# Athena-r0p1.net
KiCad netlist of a schematic drawn in EAGLE
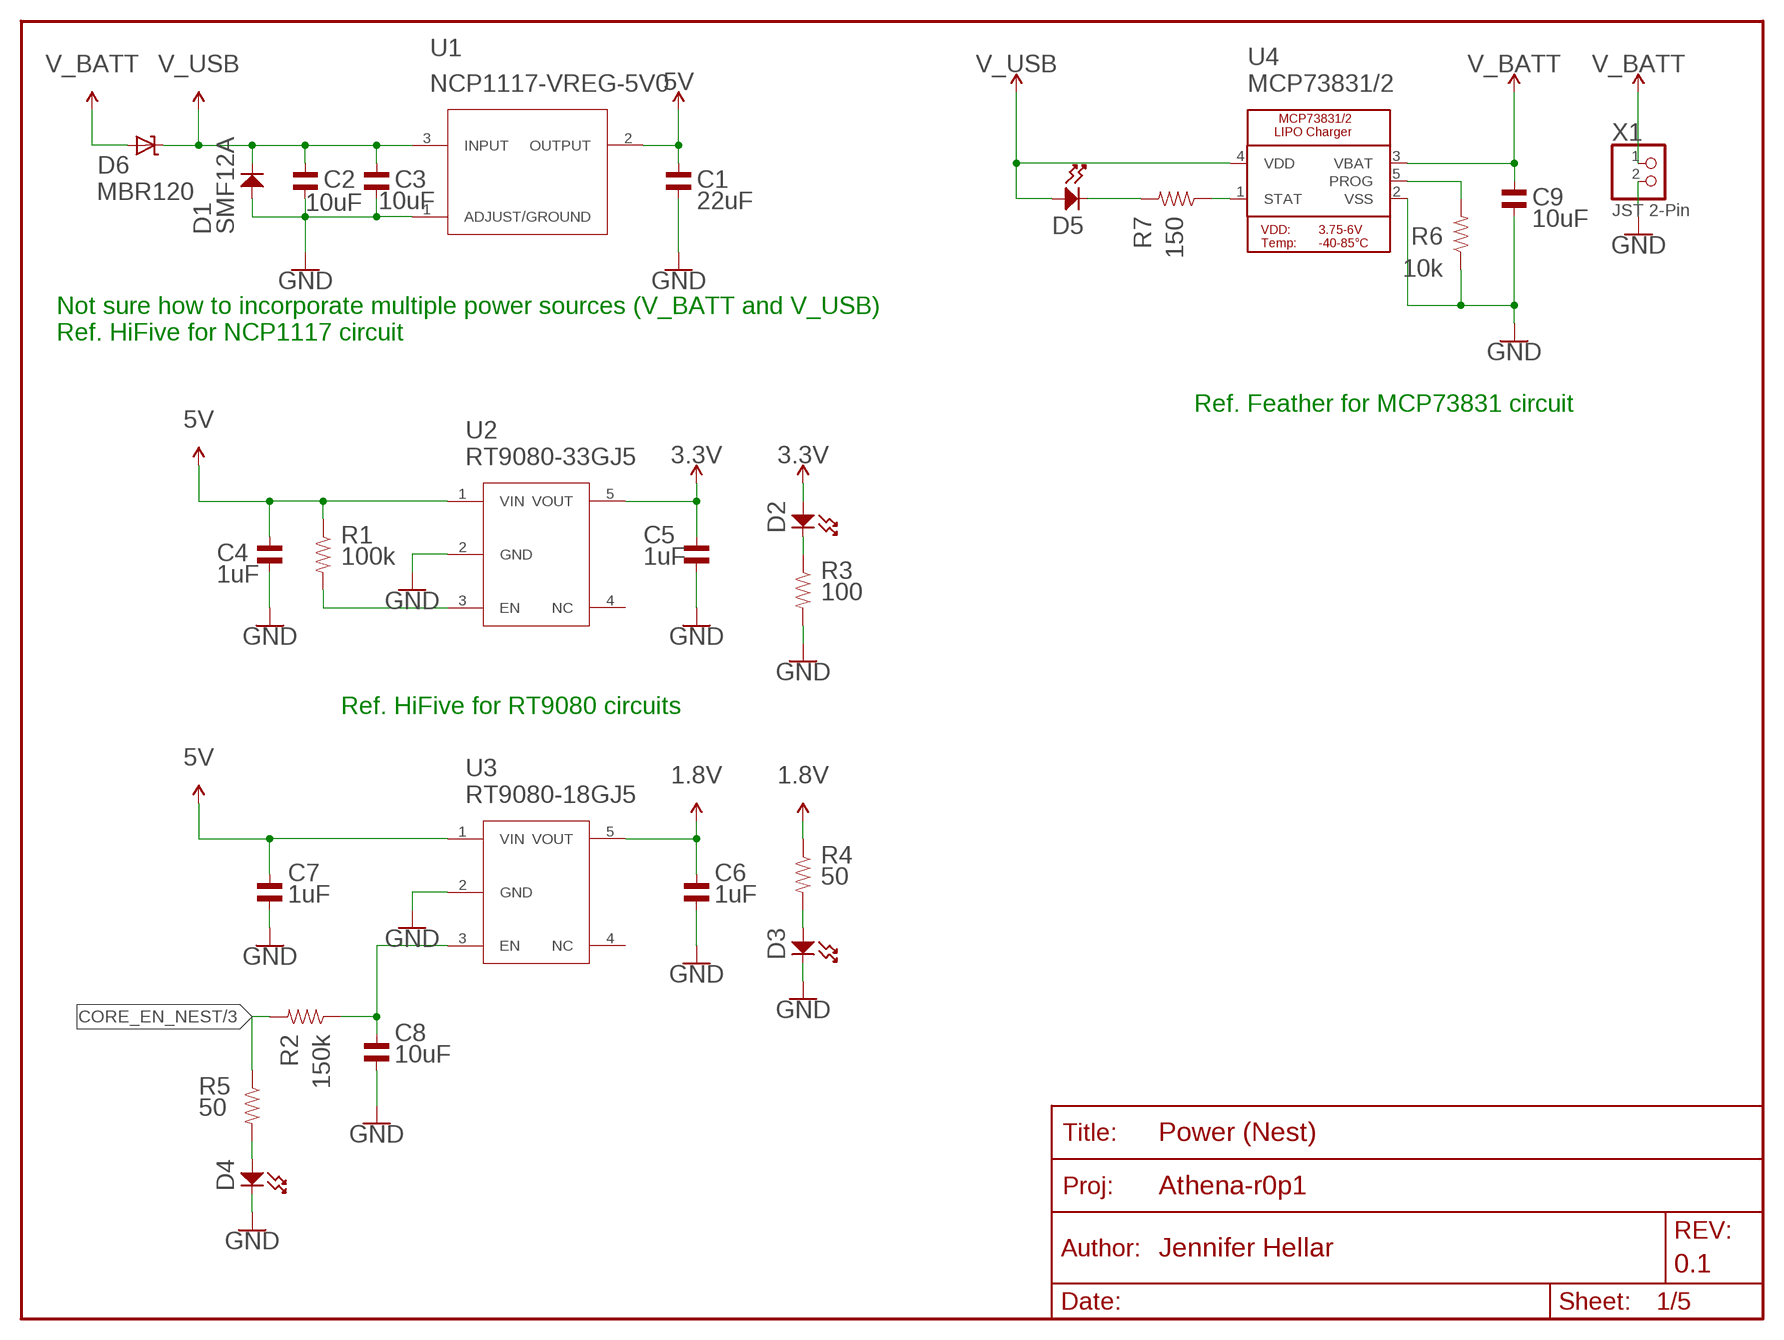
[diagram p0: schematic, sheet 1]
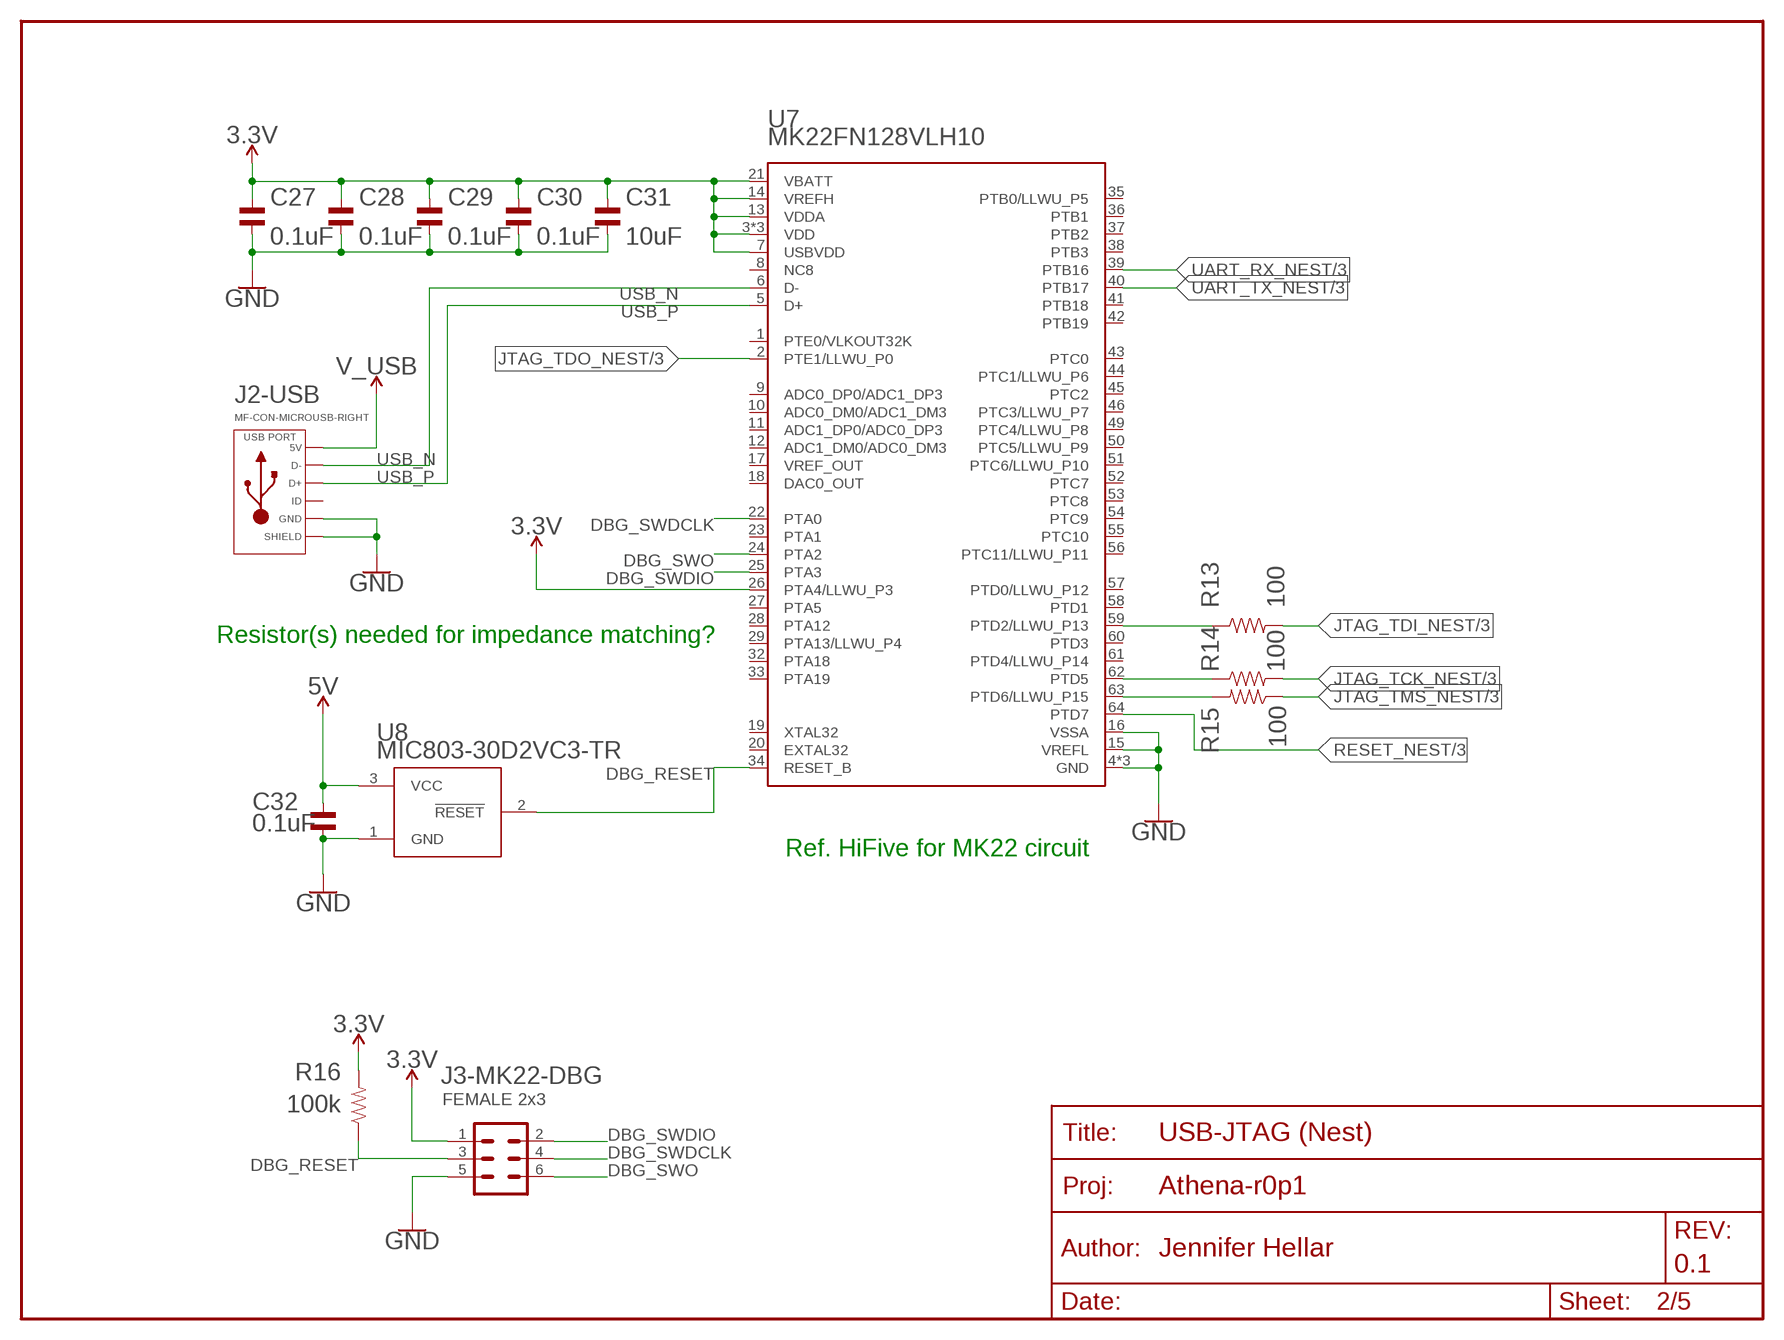
[diagram p1: schematic, sheet 2]
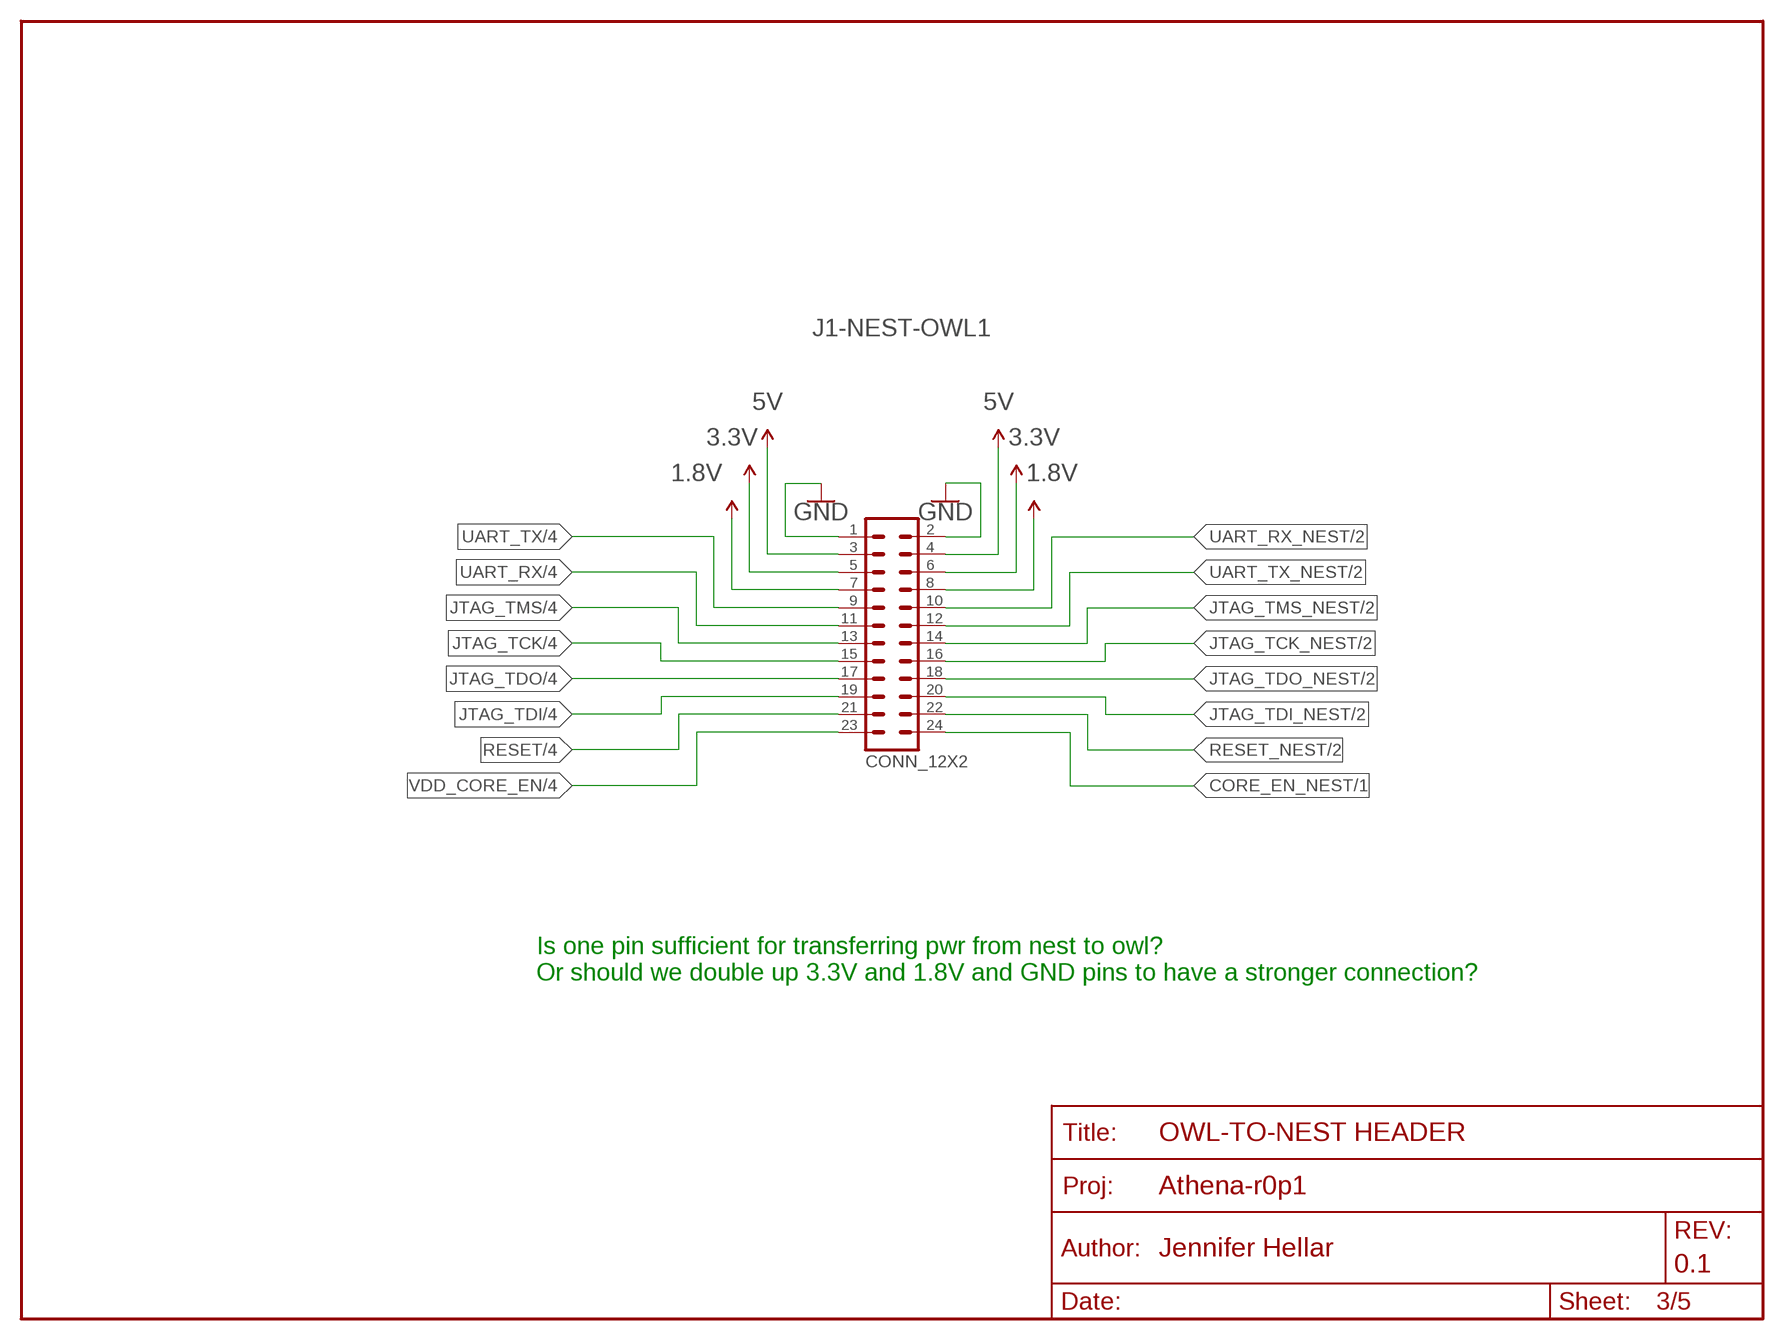
[diagram p2: schematic, sheet 3]
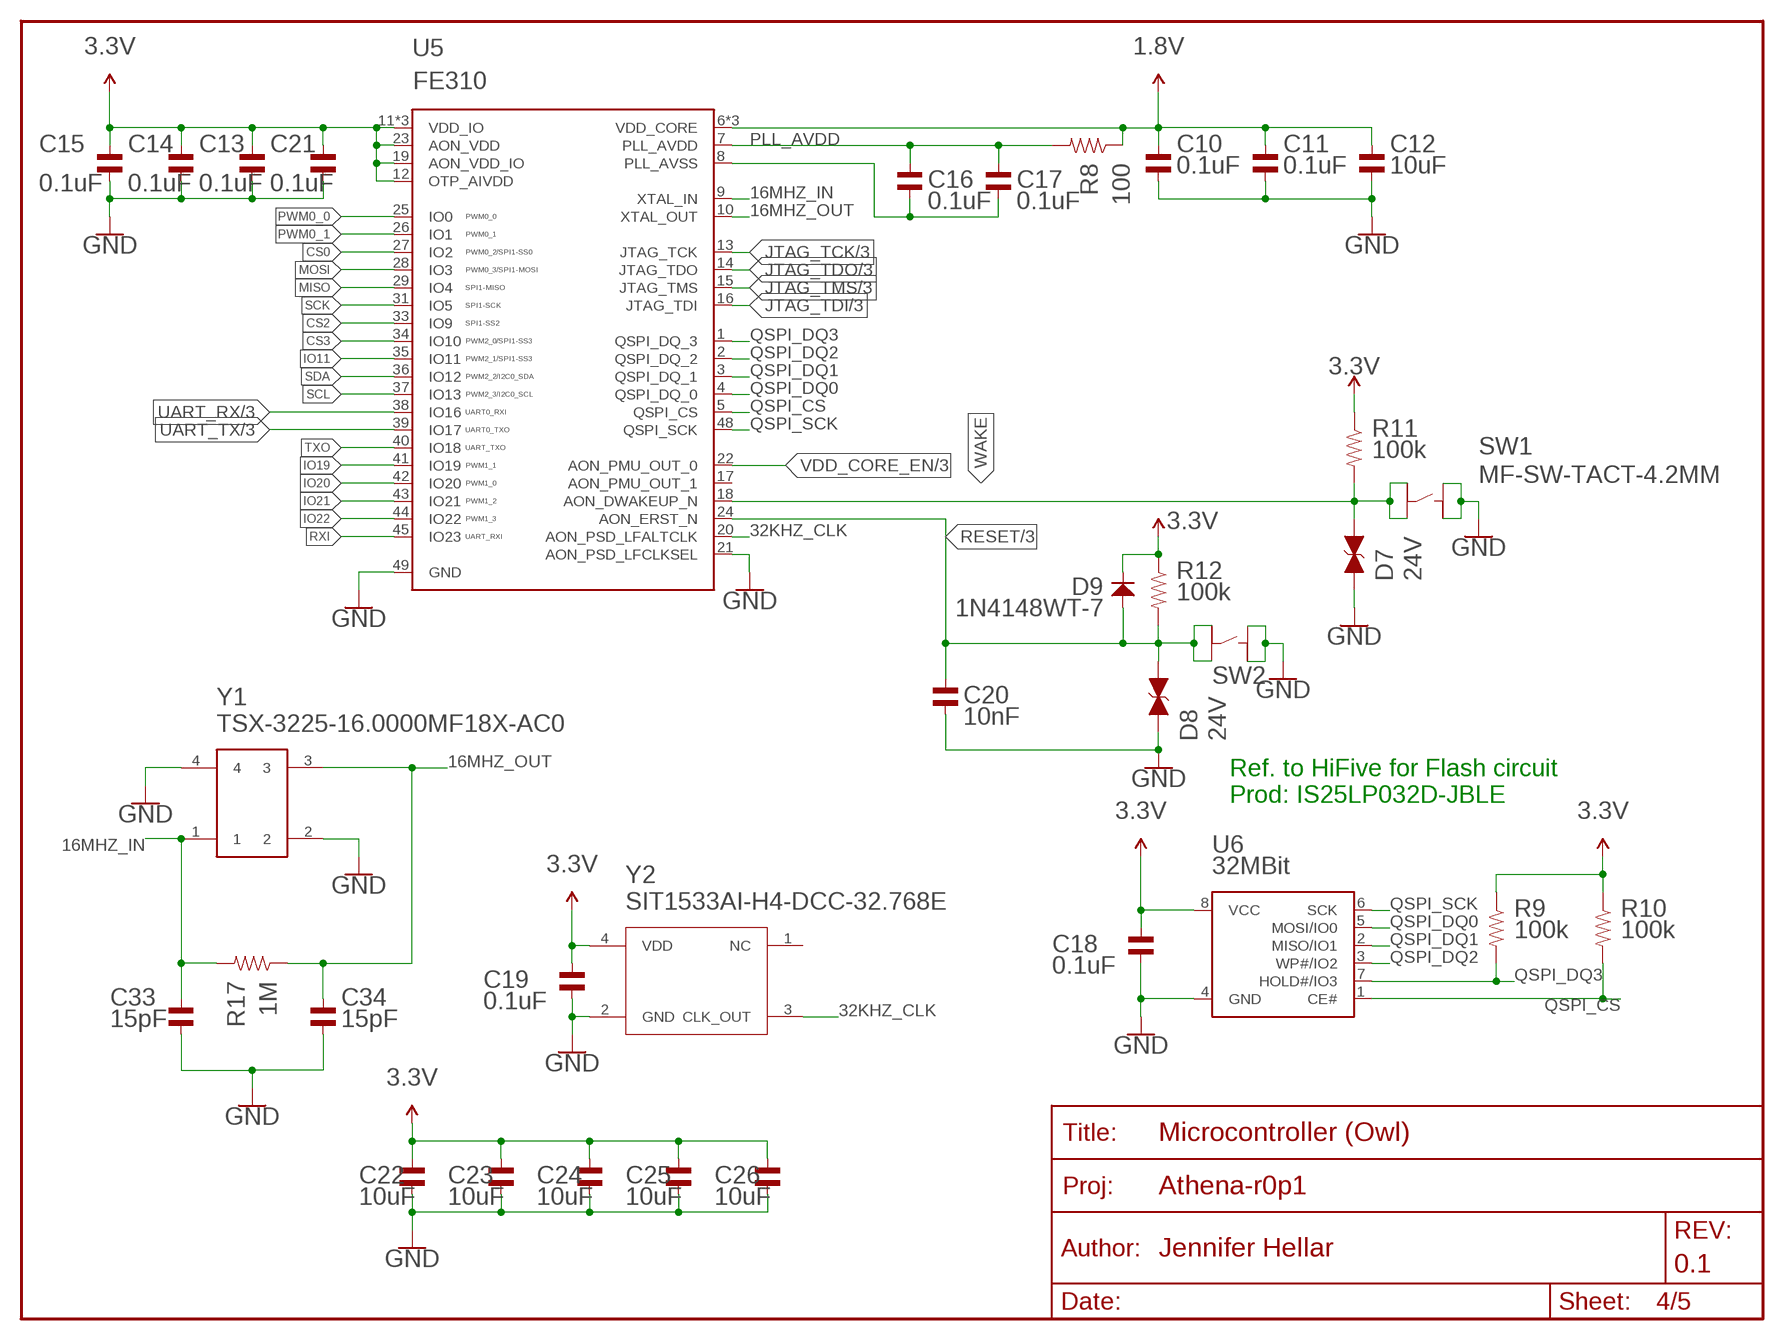
[diagram p3: schematic, sheet 4]
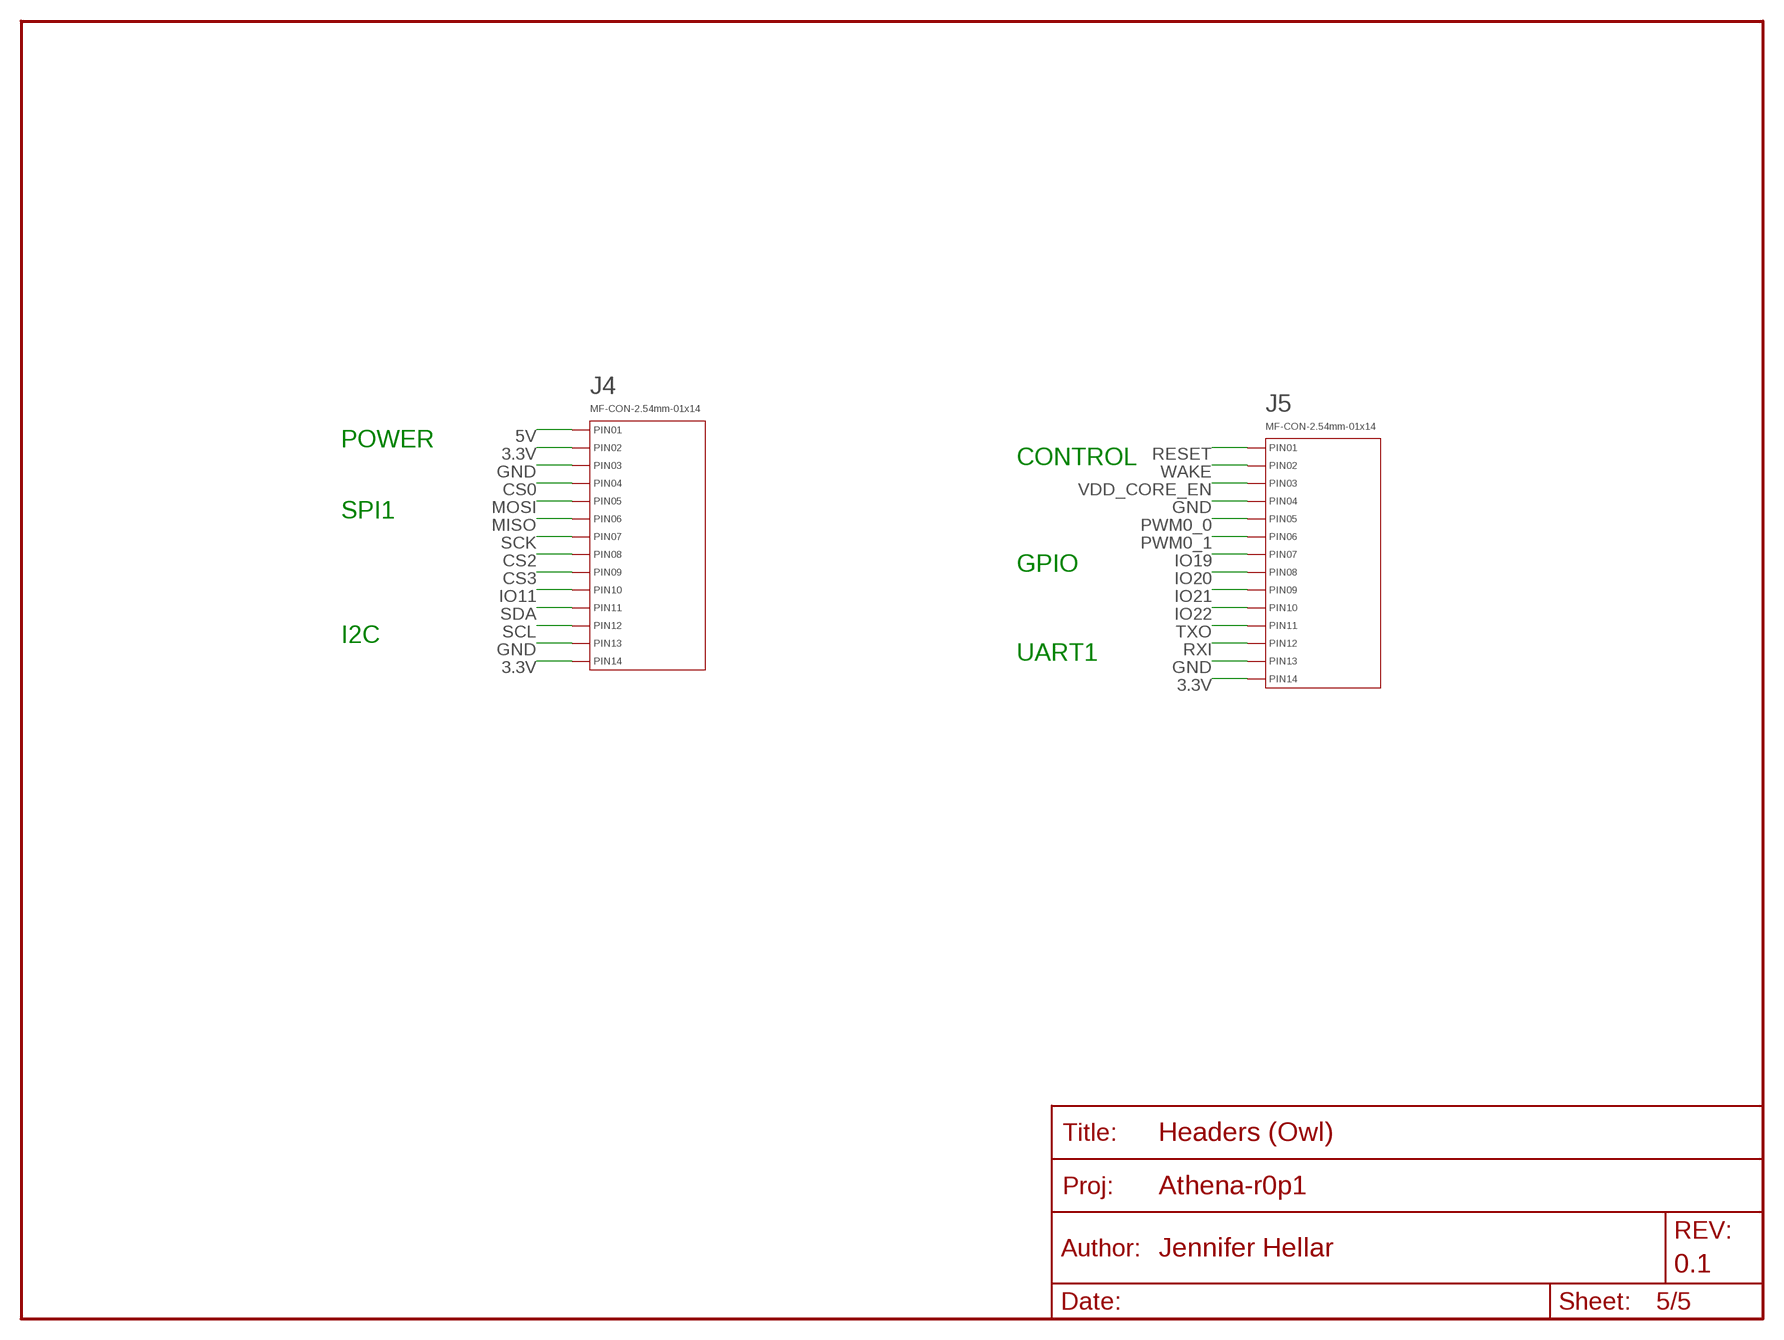
[diagram p4: schematic, sheet 5]

(export (version "E")
  (design (tool "Eeschema 10.0.6"))
  (components
    (comp (ref "C27")
      (value "0.1uF")
      (footprint "eagle-import:C0603")
      (libsource (lib "eagle-import") (part "CAPACITOR_NP_0603"))
    )
    (comp (ref "C28")
      (value "0.1uF")
      (footprint "eagle-import:C0603")
      (libsource (lib "eagle-import") (part "CAPACITOR_NP_0603"))
    )
    (comp (ref "C29")
      (value "0.1uF")
      (footprint "eagle-import:C0603")
      (libsource (lib "eagle-import") (part "CAPACITOR_NP_0603"))
    )
    (comp (ref "C30")
      (value "0.1uF")
      (footprint "eagle-import:C0603")
      (libsource (lib "eagle-import") (part "CAPACITOR_NP_0603"))
    )
    (comp (ref "C31")
      (value "10uF")
      (footprint "eagle-import:C0603")
      (libsource (lib "eagle-import") (part "CAPACITOR_NP_0603"))
    )
    (comp (ref "C32")
      (value "0.1uF")
      (footprint "eagle-import:C0603")
      (libsource (lib "eagle-import") (part "CAPACITOR_NP_0603"))
    )
    (comp (ref "FRAME3")
      (value "FRAME-LETTER")
      (footprint "eagle-import:SPARKFUN-AESTHETICS_CREATIVE_COMMONS")
      (fields
        (field (name "DESIGNER") "Jennifer Hellar")
        (field (name "REV") "0.1")
        (field (name "SHEETNM") "USB-JTAG (Nest)")
        (field (name "DESIGNER_1") "Jennifer Hellar")
      )
      (libsource (lib "eagle-import") (part "FRAME-LETTER"))
    )
    (comp (ref "J2-USB")
      (value "MF-CON-MICROUSB-RIGHT")
      (footprint "eagle-import:MICROUSB-RIGHT")
      (fields (field (name "HOUSEPART") "YES"))
      (libsource (lib "eagle-import") (part "USB_MICRO_RIGHT"))
    )
    (comp (ref "J3-MK22-DBG")
      (value "FEMALE 2x3")
      (footprint "eagle-import:2X3")
      (libsource (lib "eagle-import") (part "CONN_03X2FEMALE"))
    )
    (comp (ref "R13")
      (value "100")
      (footprint "eagle-import:R0603")
      (libsource (lib "eagle-import") (part "RESISTOR_0603"))
    )
    (comp (ref "R14")
      (value "100")
      (footprint "eagle-import:R0603")
      (libsource (lib "eagle-import") (part "RESISTOR_0603"))
    )
    (comp (ref "R15")
      (value "100")
      (footprint "eagle-import:R0603")
      (libsource (lib "eagle-import") (part "RESISTOR_0603"))
    )
    (comp (ref "R16")
      (value "100k")
      (footprint "eagle-import:R0603")
      (libsource (lib "eagle-import") (part "RESISTOR_0603"))
    )
    (comp (ref "U7")
      (value "MK22FN128VLH10")
      (footprint "eagle-import:IC_USB_JTAG_LQFP-64")
      (libsource (lib "eagle-import") (part "IC_USB_JTAG_MK22FN128VLH10"))
    )
    (comp (ref "U8")
      (value "MIC803-30D2VC3-TR")
      (footprint "eagle-import:SC-70_C3_MCH")
      (fields (field (name "COPYRIGHT") "Copyright (C) 2018 Accelerated Designs. All rights reserved"))
      (libsource (lib "eagle-import") (part "MIC803-30D2VC3-TR"))
    )
    (comp (ref "FRAME4")
      (value "FRAME-LETTER")
      (footprint "eagle-import:SPARKFUN-AESTHETICS_CREATIVE_COMMONS")
      (fields
        (field (name "DESIGNER") "Jennifer Hellar")
        (field (name "REV") "0.1")
        (field (name "SHEETNM") "Headers (Owl)")
        (field (name "DESIGNER_1") "Jennifer Hellar")
      )
      (libsource (lib "eagle-import") (part "FRAME-LETTER"))
    )
    (comp (ref "J4")
      (value "MF-CON-2.54mm-01x14")
      (footprint "eagle-import:PTH_2.54MM_01X14")
      (fields (field (name "HOUSEPART") "YES"))
      (libsource (lib "eagle-import") (part "CON_01X14_PTH_2.54MM"))
    )
    (comp (ref "J5")
      (value "MF-CON-2.54mm-01x14")
      (footprint "eagle-import:PTH_2.54MM_01X14")
      (fields (field (name "HOUSEPART") "YES"))
      (libsource (lib "eagle-import") (part "CON_01X14_PTH_2.54MM"))
    )
    (comp (ref "FRAME5")
      (value "FRAME-LETTER")
      (footprint "eagle-import:SPARKFUN-AESTHETICS_CREATIVE_COMMONS")
      (fields
        (field (name "DESIGNER") "Nobody")
        (field (name "DESIGNER_1") "Jennifer Hellar")
        (field (name "REV") "0.1")
        (field (name "SHEETNM") "OWL-TO-NEST HEADER")
      )
      (libsource (lib "eagle-import") (part "FRAME-LETTER"))
    )
    (comp (ref "J1-NEST-OWL1")
      (value "CONN_12X2")
      (footprint "eagle-import:2X12")
      (libsource (lib "eagle-import") (part "CONN_12X2"))
    )
    (comp (ref "C1")
      (value "22uF")
      (footprint "eagle-import:C0603")
      (libsource (lib "eagle-import") (part "CAPACITOR_NP_0603"))
    )
    (comp (ref "C2")
      (value "10uF")
      (footprint "eagle-import:C0603")
      (libsource (lib "eagle-import") (part "CAPACITOR_NP_0603"))
    )
    (comp (ref "C3")
      (value "10uF")
      (footprint "eagle-import:C0603")
      (libsource (lib "eagle-import") (part "CAPACITOR_NP_0603"))
    )
    (comp (ref "C4")
      (value "1uF")
      (footprint "eagle-import:C0603")
      (libsource (lib "eagle-import") (part "CAPACITOR_NP_0603"))
    )
    (comp (ref "C5")
      (value "1uF")
      (footprint "eagle-import:C0603")
      (libsource (lib "eagle-import") (part "CAPACITOR_NP_0603"))
    )
    (comp (ref "C6")
      (value "1uF")
      (footprint "eagle-import:C0603")
      (libsource (lib "eagle-import") (part "CAPACITOR_NP_0603"))
    )
    (comp (ref "C7")
      (value "1uF")
      (footprint "eagle-import:C0603")
      (libsource (lib "eagle-import") (part "CAPACITOR_NP_0603"))
    )
    (comp (ref "C8")
      (value "10uF")
      (footprint "eagle-import:C0603")
      (libsource (lib "eagle-import") (part "CAPACITOR_NP_0603"))
    )
    (comp (ref "C9")
      (value "10uF")
      (footprint "eagle-import:C0603")
      (libsource (lib "eagle-import") (part "CAPACITOR_NP_0603"))
    )
    (comp (ref "D1")
      (value "SMF12A")
      (footprint "eagle-import:SMFSERIES_LTF")
      (libsource (lib "eagle-import") (part "SMF12A"))
    )
    (comp (ref "D2")
      (value "MF-LED-0603-GREEN")
      (footprint "eagle-import:LED0603")
      (fields (field (name "HOUSEPART") "YES"))
      (libsource (lib "eagle-import") (part "LED_SINGLE-0603-GREEN"))
    )
    (comp (ref "D3")
      (value "MF-LED-0603-GREEN")
      (footprint "eagle-import:LED0603")
      (fields (field (name "HOUSEPART") "YES"))
      (libsource (lib "eagle-import") (part "LED_SINGLE-0603-GREEN"))
    )
    (comp (ref "D4")
      (value "MF-LED-0603-GREEN")
      (footprint "eagle-import:LED0603")
      (fields (field (name "HOUSEPART") "YES"))
      (libsource (lib "eagle-import") (part "LED_SINGLE-0603-GREEN"))
    )
    (comp (ref "D5")
      (value "MF-LED-0603-RED")
      (footprint "eagle-import:LED0603")
      (fields (field (name "HOUSEPART") "YES"))
      (libsource (lib "eagle-import") (part "LED_SINGLE-0603-RED"))
    )
    (comp (ref "D6")
      (value "MBR120")
      (footprint "eagle-import:SOD-123")
      (libsource (lib "eagle-import") (part "DIODE-SCHOTTKYSOD-123"))
    )
    (comp (ref "FRAME1")
      (value "FRAME-LETTER")
      (footprint "eagle-import:SPARKFUN-AESTHETICS_CREATIVE_COMMONS")
      (fields
        (field (name "DESIGNER") "Jennifer Hellar")
        (field (name "REV") "0.1")
        (field (name "SHEETNM") "Power (Nest)")
        (field (name "DESIGNER_1") "Jennifer Hellar")
      )
      (libsource (lib "eagle-import") (part "FRAME-LETTER"))
    )
    (comp (ref "R1")
      (value "100k")
      (footprint "eagle-import:R0603")
      (libsource (lib "eagle-import") (part "RESISTOR_0603"))
    )
    (comp (ref "R2")
      (value "150k")
      (footprint "eagle-import:R0603")
      (libsource (lib "eagle-import") (part "RESISTOR_0603"))
    )
    (comp (ref "R3")
      (value "100")
      (footprint "eagle-import:R0603")
      (libsource (lib "eagle-import") (part "RESISTOR_0603"))
    )
    (comp (ref "R4")
      (value "50")
      (footprint "eagle-import:R0603")
      (libsource (lib "eagle-import") (part "RESISTOR_0603"))
    )
    (comp (ref "R5")
      (value "50")
      (footprint "eagle-import:R0603")
      (libsource (lib "eagle-import") (part "RESISTOR_0603"))
    )
    (comp (ref "R6")
      (value "10k")
      (footprint "eagle-import:R0603")
      (libsource (lib "eagle-import") (part "RESISTOR_0603"))
    )
    (comp (ref "R7")
      (value "150")
      (footprint "eagle-import:R0603")
      (libsource (lib "eagle-import") (part "RESISTOR_0603"))
    )
    (comp (ref "U1")
      (value "NCP1117-VREG-5V0")
      (footprint "eagle-import:SOT223-3_ONS")
      (fields
        (field (name "MANUFACTURER_PART_NUMBER") "NCP1117LPST50T3G")
        (field (name "COPYRIGHT") "Copyright (C) 2016 Accelerated Designs. All rights reserved")
      )
      (libsource (lib "eagle-import") (part "NCP1117LPST50T3G"))
    )
    (comp (ref "U2")
      (value "RT9080-33GJ5")
      (footprint "eagle-import:TSOT23-5_ONS")
      (libsource (lib "eagle-import") (part "RT9080-33GJ5"))
    )
    (comp (ref "U3")
      (value "RT9080-18GJ5")
      (footprint "eagle-import:TSOT23-5_ONS")
      (libsource (lib "eagle-import") (part "RT9080-18GJ5"))
    )
    (comp (ref "U4")
      (value "MCP73831/2")
      (footprint "eagle-import:SOT23-5")
      (libsource (lib "eagle-import") (part "IC_POWER_LIPO_MCP73831/2"))
    )
    (comp (ref "X1")
      (value "JST 2-Pin")
      (footprint "eagle-import:JSTPH2")
      (libsource (lib "eagle-import") (part "CONNECTORS_BATT_JST_PH_2PIN"))
    )
    (comp (ref "C10")
      (value "0.1uF")
      (footprint "eagle-import:C0603")
      (libsource (lib "eagle-import") (part "CAPACITOR_NP_0603"))
    )
    (comp (ref "C11")
      (value "0.1uF")
      (footprint "eagle-import:C0603")
      (libsource (lib "eagle-import") (part "CAPACITOR_NP_0603"))
    )
    (comp (ref "C12")
      (value "10uF")
      (footprint "eagle-import:C0603")
      (libsource (lib "eagle-import") (part "CAPACITOR_NP_0603"))
    )
    (comp (ref "C13")
      (value "0.1uF")
      (footprint "eagle-import:C0603")
      (libsource (lib "eagle-import") (part "CAPACITOR_NP_0603"))
    )
    (comp (ref "C14")
      (value "0.1uF")
      (footprint "eagle-import:C0603")
      (libsource (lib "eagle-import") (part "CAPACITOR_NP_0603"))
    )
    (comp (ref "C15")
      (value "0.1uF")
      (footprint "eagle-import:C0603")
      (libsource (lib "eagle-import") (part "CAPACITOR_NP_0603"))
    )
    (comp (ref "C16")
      (value "0.1uF")
      (footprint "eagle-import:C0603")
      (libsource (lib "eagle-import") (part "CAPACITOR_NP_0603"))
    )
    (comp (ref "C17")
      (value "0.1uF")
      (footprint "eagle-import:C0603")
      (libsource (lib "eagle-import") (part "CAPACITOR_NP_0603"))
    )
    (comp (ref "C18")
      (value "0.1uF")
      (footprint "eagle-import:C0603")
      (libsource (lib "eagle-import") (part "CAPACITOR_NP_0603"))
    )
    (comp (ref "C19")
      (value "0.1uF")
      (footprint "eagle-import:C0603")
      (libsource (lib "eagle-import") (part "CAPACITOR_NP_0603"))
    )
    (comp (ref "C20")
      (value "10nF")
      (footprint "eagle-import:C0603")
      (libsource (lib "eagle-import") (part "CAPACITOR_NP_0603"))
    )
    (comp (ref "C21")
      (value "0.1uF")
      (footprint "eagle-import:C0603")
      (libsource (lib "eagle-import") (part "CAPACITOR_NP_0603"))
    )
    (comp (ref "C22")
      (value "10uF")
      (footprint "eagle-import:C0603")
      (libsource (lib "eagle-import") (part "CAPACITOR_NP_0603"))
    )
    (comp (ref "C23")
      (value "10uF")
      (footprint "eagle-import:C0603")
      (libsource (lib "eagle-import") (part "CAPACITOR_NP_0603"))
    )
    (comp (ref "C24")
      (value "10uF")
      (footprint "eagle-import:C0603")
      (libsource (lib "eagle-import") (part "CAPACITOR_NP_0603"))
    )
    (comp (ref "C25")
      (value "10uF")
      (footprint "eagle-import:C0603")
      (libsource (lib "eagle-import") (part "CAPACITOR_NP_0603"))
    )
    (comp (ref "C26")
      (value "10uF")
      (footprint "eagle-import:C0603")
      (libsource (lib "eagle-import") (part "CAPACITOR_NP_0603"))
    )
    (comp (ref "C33")
      (value "15pF")
      (footprint "eagle-import:C0603")
      (libsource (lib "eagle-import") (part "CAPACITOR_NP_0603"))
    )
    (comp (ref "C34")
      (value "15pF")
      (footprint "eagle-import:C0603")
      (libsource (lib "eagle-import") (part "CAPACITOR_NP_0603"))
    )
    (comp (ref "D7")
      (value "24V")
      (footprint "eagle-import:SPARKFUN-DISCRETESEMI_0603")
      (libsource (lib "eagle-import") (part "SPARKFUN-DISCRETESEMI_DIODE_TVS"))
    )
    (comp (ref "D8")
      (value "24V")
      (footprint "eagle-import:SPARKFUN-DISCRETESEMI_0603")
      (libsource (lib "eagle-import") (part "SPARKFUN-DISCRETESEMI_DIODE_TVS"))
    )
    (comp (ref "D9")
      (value "1N4148WT-7")
      (footprint "eagle-import:SOD-523")
      (fields (field (name "COPYRIGHT") "Copyright (C) 2016 Accelerated Designs. All rights reserved"))
      (libsource (lib "eagle-import") (part "1N4148WT-7"))
    )
    (comp (ref "FRAME2")
      (value "FRAME-LETTER")
      (footprint "eagle-import:SPARKFUN-AESTHETICS_CREATIVE_COMMONS")
      (fields
        (field (name "DESIGNER") "Jennifer Hellar")
        (field (name "REV") "0.1")
        (field (name "SHEETNM") "Microcontroller (Owl)")
        (field (name "DESIGNER_1") "Jennifer Hellar")
      )
      (libsource (lib "eagle-import") (part "FRAME-LETTER"))
    )
    (comp (ref "R8")
      (value "100")
      (footprint "eagle-import:R0603")
      (libsource (lib "eagle-import") (part "RESISTOR_0603"))
    )
    (comp (ref "R9")
      (value "100k")
      (footprint "eagle-import:R0603")
      (libsource (lib "eagle-import") (part "RESISTOR_0603"))
    )
    (comp (ref "R10")
      (value "100k")
      (footprint "eagle-import:R0603")
      (libsource (lib "eagle-import") (part "RESISTOR_0603"))
    )
    (comp (ref "R11")
      (value "100k")
      (footprint "eagle-import:R0603")
      (libsource (lib "eagle-import") (part "RESISTOR_0603"))
    )
    (comp (ref "R12")
      (value "100k")
      (footprint "eagle-import:R0603")
      (libsource (lib "eagle-import") (part "RESISTOR_0603"))
    )
    (comp (ref "R17")
      (value "1M")
      (footprint "eagle-import:R0603")
      (libsource (lib "eagle-import") (part "RESISTOR_0603"))
    )
    (comp (ref "SW1")
      (value "MF-SW-TACT-4.2MM")
      (footprint "eagle-import:TACT4.2MM")
      (fields (field (name "HOUSEPART") "YES"))
      (libsource (lib "eagle-import") (part "TACT_4.2MM"))
    )
    (comp (ref "SW2")
      (value "MF-SW-TACT-4.2MM")
      (footprint "eagle-import:TACT4.2MM")
      (fields (field (name "HOUSEPART") "YES"))
      (libsource (lib "eagle-import") (part "TACT_4.2MM"))
    )
    (comp (ref "U5")
      (value "FE310")
      (footprint "eagle-import:MCU_QFN-48-.4MMPITCH")
      (libsource (lib "eagle-import") (part "IC_MCU_SIFIVE_FE310"))
    )
    (comp (ref "U6")
      (value "32MBit")
      (footprint "eagle-import:IC-MEMORY_SO08")
      (libsource (lib "eagle-import") (part "IC_MEMORY_QSPI32MBIT"))
    )
    (comp (ref "Y1")
      (value "TSX-3225-16.0000MF18X-AC0")
      (footprint "eagle-import:TSX-3225")
      (libsource (lib "eagle-import") (part "TSX-3225-16.0000MF18X-AC0"))
    )
    (comp (ref "Y2")
      (value "SIT1533AI-H4-DCC-32.768E")
      (footprint "eagle-import:XTAL4_SIT1533_SIT")
      (fields (field (name "COPYRIGHT") "Copyright (C) 2018 Accelerated Designs. All rights reserved"))
      (libsource (lib "eagle-import") (part "SIT1533AI-H4-DCC-32.768E"))
    )
  )
  (nets
    (net (code "1") (name "1.8V") (class "Default")
      (node (ref "C10") (pin "P$1") (pinfunction "P$1_P$1") (pintype "passive"))
      (node (ref "C11") (pin "P$1") (pinfunction "P$1_P$1") (pintype "passive"))
      (node (ref "C12") (pin "P$1") (pinfunction "P$1_P$1") (pintype "passive"))
      (node (ref "C6") (pin "P$1") (pinfunction "P$1_P$1") (pintype "passive"))
      (node (ref "J1-NEST-OWL1") (pin "7") (pinfunction "7_7") (pintype "passive"))
      (node (ref "J1-NEST-OWL1") (pin "8") (pinfunction "8_8") (pintype "passive"))
      (node (ref "R4") (pin "P$1") (pinfunction "P$1_P$1") (pintype "passive"))
      (node (ref "R8") (pin "P$1") (pinfunction "P$1_P$1") (pintype "passive"))
      (node (ref "U3") (pin "5") (pinfunction "VOUT_5") (pintype "passive"))
      (node (ref "U5") (pin "30") (pinfunction "VDD_CORE_30") (pintype "bidirectional"))
      (node (ref "U5") (pin "46") (pinfunction "VDD_CORE_46") (pintype "bidirectional"))
      (node (ref "U5") (pin "6") (pinfunction "VDD_CORE_6") (pintype "bidirectional"))
    )
    (net (code "2") (name "3.3V") (class "Default")
      (node (ref "C13") (pin "P$1") (pinfunction "P$1_P$1") (pintype "passive"))
      (node (ref "C14") (pin "P$1") (pinfunction "P$1_P$1") (pintype "passive"))
      (node (ref "C15") (pin "P$1") (pinfunction "P$1_P$1") (pintype "passive"))
      (node (ref "C18") (pin "P$1") (pinfunction "P$1_P$1") (pintype "passive"))
      (node (ref "C19") (pin "P$1") (pinfunction "P$1_P$1") (pintype "passive"))
      (node (ref "C21") (pin "P$1") (pinfunction "P$1_P$1") (pintype "passive"))
      (node (ref "C22") (pin "P$1") (pinfunction "P$1_P$1") (pintype "passive"))
      (node (ref "C23") (pin "P$1") (pinfunction "P$1_P$1") (pintype "passive"))
      (node (ref "C24") (pin "P$1") (pinfunction "P$1_P$1") (pintype "passive"))
      (node (ref "C25") (pin "P$1") (pinfunction "P$1_P$1") (pintype "passive"))
      (node (ref "C26") (pin "P$1") (pinfunction "P$1_P$1") (pintype "passive"))
      (node (ref "C27") (pin "P$1") (pinfunction "P$1_P$1") (pintype "passive"))
      (node (ref "C28") (pin "P$1") (pinfunction "P$1_P$1") (pintype "passive"))
      (node (ref "C29") (pin "P$1") (pinfunction "P$1_P$1") (pintype "passive"))
      (node (ref "C30") (pin "P$1") (pinfunction "P$1_P$1") (pintype "passive"))
      (node (ref "C31") (pin "P$1") (pinfunction "P$1_P$1") (pintype "passive"))
      (node (ref "C5") (pin "P$1") (pinfunction "P$1_P$1") (pintype "passive"))
      (node (ref "D2") (pin "ANODE") (pinfunction "ANODE_ANODE") (pintype "power_in"))
      (node (ref "D9") (pin "K") (pinfunction "CATHODE_K") (pintype "bidirectional"))
      (node (ref "J1-NEST-OWL1") (pin "5") (pinfunction "5_5") (pintype "passive"))
      (node (ref "J1-NEST-OWL1") (pin "6") (pinfunction "6_6") (pintype "passive"))
      (node (ref "J3-MK22-DBG") (pin "1") (pinfunction "1_1") (pintype "bidirectional"))
      (node (ref "J4") (pin "P$14") (pinfunction "PIN14_P$14") (pintype "bidirectional"))
      (node (ref "J4") (pin "P$2") (pinfunction "PIN2_P$2") (pintype "bidirectional"))
      (node (ref "J5") (pin "P$14") (pinfunction "PIN14_P$14") (pintype "bidirectional"))
      (node (ref "R10") (pin "P$1") (pinfunction "P$1_P$1") (pintype "passive"))
      (node (ref "R11") (pin "P$1") (pinfunction "P$1_P$1") (pintype "passive"))
      (node (ref "R12") (pin "P$1") (pinfunction "P$1_P$1") (pintype "passive"))
      (node (ref "R16") (pin "P$2") (pinfunction "P$2_P$2") (pintype "passive"))
      (node (ref "R9") (pin "P$1") (pinfunction "P$1_P$1") (pintype "passive"))
      (node (ref "U2") (pin "5") (pinfunction "VOUT_5") (pintype "passive"))
      (node (ref "U5") (pin "11") (pinfunction "VDD_IO_11") (pintype "bidirectional"))
      (node (ref "U5") (pin "12") (pinfunction "OTP_AIVDD_12") (pintype "bidirectional"))
      (node (ref "U5") (pin "19") (pinfunction "AON_VDD_IO_19") (pintype "bidirectional"))
      (node (ref "U5") (pin "23") (pinfunction "AON_VDD_23") (pintype "bidirectional"))
      (node (ref "U5") (pin "32") (pinfunction "VDD_IO_32") (pintype "bidirectional"))
      (node (ref "U5") (pin "47") (pinfunction "VDD_IO_47") (pintype "bidirectional"))
      (node (ref "U6") (pin "8") (pinfunction "VCC_8") (pintype "bidirectional"))
      (node (ref "U7") (pin "13") (pinfunction "VDDA_13") (pintype "bidirectional"))
      (node (ref "U7") (pin "14") (pinfunction "VREFH_14") (pintype "bidirectional"))
      (node (ref "U7") (pin "21") (pinfunction "VBATT_21") (pintype "bidirectional"))
      (node (ref "U7") (pin "26") (pinfunction "PTA4/LLWU_P3_26") (pintype "bidirectional"))
      (node (ref "U7") (pin "3") (pinfunction "VDD_3") (pintype "bidirectional"))
      (node (ref "U7") (pin "30") (pinfunction "VDD_30") (pintype "bidirectional"))
      (node (ref "U7") (pin "48") (pinfunction "VDD_48") (pintype "bidirectional"))
      (node (ref "U7") (pin "7") (pinfunction "USBVDD_7") (pintype "bidirectional"))
      (node (ref "Y2") (pin "4") (pinfunction "VDD_4") (pintype "power_in"))
    )
    (net (code "3") (name "5V") (class "Default")
      (node (ref "C1") (pin "P$1") (pinfunction "P$1_P$1") (pintype "passive"))
      (node (ref "C32") (pin "P$1") (pinfunction "P$1_P$1") (pintype "passive"))
      (node (ref "C4") (pin "P$1") (pinfunction "P$1_P$1") (pintype "passive"))
      (node (ref "C7") (pin "P$1") (pinfunction "P$1_P$1") (pintype "passive"))
      (node (ref "J1-NEST-OWL1") (pin "3") (pinfunction "3_3") (pintype "passive"))
      (node (ref "J1-NEST-OWL1") (pin "4") (pinfunction "4_4") (pintype "passive"))
      (node (ref "J4") (pin "P$1") (pinfunction "PIN1_P$1") (pintype "bidirectional"))
      (node (ref "R1") (pin "P$1") (pinfunction "P$1_P$1") (pintype "passive"))
      (node (ref "U1") (pin "2") (pinfunction "OUTPUT_2") (pintype "output"))
      (node (ref "U2") (pin "1") (pinfunction "VIN_1") (pintype "passive"))
      (node (ref "U3") (pin "1") (pinfunction "VIN_1") (pintype "passive"))
      (node (ref "U8") (pin "3") (pinfunction "VCC_3") (pintype "power_in"))
    )
    (net (code "4") (name "16MHZ_IN") (class "Default")
      (node (ref "C33") (pin "P$1") (pinfunction "P$1_P$1") (pintype "passive"))
      (node (ref "R17") (pin "P$2") (pinfunction "P$2_P$2") (pintype "passive"))
      (node (ref "U5") (pin "9") (pinfunction "XTAL_IN_9") (pintype "bidirectional"))
      (node (ref "Y1") (pin "1") (pinfunction "1_1") (pintype "passive"))
    )
    (net (code "5") (name "16MHZ_OUT") (class "Default")
      (node (ref "C34") (pin "P$1") (pinfunction "P$1_P$1") (pintype "passive"))
      (node (ref "R17") (pin "P$1") (pinfunction "P$1_P$1") (pintype "passive"))
      (node (ref "U5") (pin "10") (pinfunction "XTAL_OUT_10") (pintype "bidirectional"))
      (node (ref "Y1") (pin "3") (pinfunction "3_3") (pintype "passive"))
    )
    (net (code "6") (name "32KHZ_CLK") (class "Default")
      (node (ref "U5") (pin "20") (pinfunction "AON_PSD_LFALTCLK_20") (pintype "bidirectional"))
      (node (ref "Y2") (pin "3") (pinfunction "CLK_OUT_3") (pintype "output"))
    )
    (net (code "7") (name "CORE_EN_NEST") (class "Default")
      (node (ref "J1-NEST-OWL1") (pin "24") (pinfunction "24_24") (pintype "passive"))
      (node (ref "R2") (pin "P$2") (pinfunction "P$2_P$2") (pintype "passive"))
      (node (ref "R5") (pin "P$1") (pinfunction "P$1_P$1") (pintype "passive"))
    )
    (net (code "8") (name "CS0") (class "Default")
      (node (ref "J4") (pin "P$4") (pinfunction "PIN4_P$4") (pintype "bidirectional"))
      (node (ref "U5") (pin "27") (pinfunction "IO2_27") (pintype "bidirectional"))
    )
    (net (code "9") (name "CS2") (class "Default")
      (node (ref "J4") (pin "P$8") (pinfunction "PIN8_P$8") (pintype "bidirectional"))
      (node (ref "U5") (pin "33") (pinfunction "IO9_33") (pintype "bidirectional"))
    )
    (net (code "10") (name "CS3") (class "Default")
      (node (ref "J4") (pin "P$9") (pinfunction "PIN9_P$9") (pintype "bidirectional"))
      (node (ref "U5") (pin "34") (pinfunction "IO10_34") (pintype "bidirectional"))
    )
    (net (code "11") (name "DBG_RESET") (class "Default")
      (node (ref "J3-MK22-DBG") (pin "3") (pinfunction "3_3") (pintype "bidirectional"))
      (node (ref "R16") (pin "P$1") (pinfunction "P$1_P$1") (pintype "passive"))
      (node (ref "U7") (pin "34") (pinfunction "RESET_B_34") (pintype "bidirectional"))
      (node (ref "U8") (pin "2") (pinfunction "~{RESET}_2") (pintype "passive"))
    )
    (net (code "12") (name "DBG_SWDCLK") (class "Default")
      (node (ref "J3-MK22-DBG") (pin "4") (pinfunction "4_4") (pintype "bidirectional"))
      (node (ref "U7") (pin "22") (pinfunction "PTA0_22") (pintype "bidirectional"))
    )
    (net (code "13") (name "DBG_SWDIO") (class "Default")
      (node (ref "J3-MK22-DBG") (pin "2") (pinfunction "2_2") (pintype "bidirectional"))
      (node (ref "U7") (pin "25") (pinfunction "PTA3_25") (pintype "bidirectional"))
    )
    (net (code "14") (name "DBG_SWO") (class "Default")
      (node (ref "J3-MK22-DBG") (pin "6") (pinfunction "6_6") (pintype "bidirectional"))
      (node (ref "U7") (pin "24") (pinfunction "PTA2_24") (pintype "bidirectional"))
    )
    (net (code "15") (name "GND") (class "Default")
      (node (ref "C1") (pin "P$2") (pinfunction "P$2_P$2") (pintype "passive"))
      (node (ref "C10") (pin "P$2") (pinfunction "P$2_P$2") (pintype "passive"))
      (node (ref "C11") (pin "P$2") (pinfunction "P$2_P$2") (pintype "passive"))
      (node (ref "C12") (pin "P$2") (pinfunction "P$2_P$2") (pintype "passive"))
      (node (ref "C13") (pin "P$2") (pinfunction "P$2_P$2") (pintype "passive"))
      (node (ref "C14") (pin "P$2") (pinfunction "P$2_P$2") (pintype "passive"))
      (node (ref "C15") (pin "P$2") (pinfunction "P$2_P$2") (pintype "passive"))
      (node (ref "C18") (pin "P$2") (pinfunction "P$2_P$2") (pintype "passive"))
      (node (ref "C19") (pin "P$2") (pinfunction "P$2_P$2") (pintype "passive"))
      (node (ref "C2") (pin "P$2") (pinfunction "P$2_P$2") (pintype "passive"))
      (node (ref "C20") (pin "P$2") (pinfunction "P$2_P$2") (pintype "passive"))
      (node (ref "C21") (pin "P$2") (pinfunction "P$2_P$2") (pintype "passive"))
      (node (ref "C22") (pin "P$2") (pinfunction "P$2_P$2") (pintype "passive"))
      (node (ref "C23") (pin "P$2") (pinfunction "P$2_P$2") (pintype "passive"))
      (node (ref "C24") (pin "P$2") (pinfunction "P$2_P$2") (pintype "passive"))
      (node (ref "C25") (pin "P$2") (pinfunction "P$2_P$2") (pintype "passive"))
      (node (ref "C26") (pin "P$2") (pinfunction "P$2_P$2") (pintype "passive"))
      (node (ref "C27") (pin "P$2") (pinfunction "P$2_P$2") (pintype "passive"))
      (node (ref "C28") (pin "P$2") (pinfunction "P$2_P$2") (pintype "passive"))
      (node (ref "C29") (pin "P$2") (pinfunction "P$2_P$2") (pintype "passive"))
      (node (ref "C3") (pin "P$2") (pinfunction "P$2_P$2") (pintype "passive"))
      (node (ref "C30") (pin "P$2") (pinfunction "P$2_P$2") (pintype "passive"))
      (node (ref "C31") (pin "P$2") (pinfunction "P$2_P$2") (pintype "passive"))
      (node (ref "C32") (pin "P$2") (pinfunction "P$2_P$2") (pintype "passive"))
      (node (ref "C33") (pin "P$2") (pinfunction "P$2_P$2") (pintype "passive"))
      (node (ref "C34") (pin "P$2") (pinfunction "P$2_P$2") (pintype "passive"))
      (node (ref "C4") (pin "P$2") (pinfunction "P$2_P$2") (pintype "passive"))
      (node (ref "C5") (pin "P$2") (pinfunction "P$2_P$2") (pintype "passive"))
      (node (ref "C6") (pin "P$2") (pinfunction "P$2_P$2") (pintype "passive"))
      (node (ref "C7") (pin "P$2") (pinfunction "P$2_P$2") (pintype "passive"))
      (node (ref "C8") (pin "P$2") (pinfunction "P$2_P$2") (pintype "passive"))
      (node (ref "C9") (pin "P$2") (pinfunction "P$2_P$2") (pintype "passive"))
      (node (ref "D1") (pin "2") (pinfunction "ANODE_2") (pintype "bidirectional"))
      (node (ref "D3") (pin "CATHODE") (pinfunction "CATHODE_CATHODE") (pintype "power_in"))
      (node (ref "D4") (pin "CATHODE") (pinfunction "CATHODE_CATHODE") (pintype "power_in"))
      (node (ref "D7") (pin "1") (pinfunction "A_1") (pintype "passive"))
      (node (ref "D8") (pin "1") (pinfunction "A_1") (pintype "passive"))
      (node (ref "J1-NEST-OWL1") (pin "1") (pinfunction "1_1") (pintype "passive"))
      (node (ref "J1-NEST-OWL1") (pin "2") (pinfunction "2_2") (pintype "passive"))
      (node (ref "J2-USB") (pin "5") (pinfunction "GND_5") (pintype "power_in"))
      (node (ref "J2-USB") (pin "S1") (pinfunction "SLD_S1") (pintype "power_in"))
      (node (ref "J2-USB") (pin "S2") (pinfunction "SLD_S2") (pintype "power_in"))
      (node (ref "J2-USB") (pin "S3") (pinfunction "SLD_S3") (pintype "power_in"))
      (node (ref "J2-USB") (pin "S4") (pinfunction "SLD_S4") (pintype "power_in"))
      (node (ref "J2-USB") (pin "S5") (pinfunction "SLD_S5") (pintype "power_in"))
      (node (ref "J2-USB") (pin "S6") (pinfunction "SLD_S6") (pintype "power_in"))
      (node (ref "J3-MK22-DBG") (pin "5") (pinfunction "5_5") (pintype "bidirectional"))
      (node (ref "J4") (pin "P$13") (pinfunction "PIN13_P$13") (pintype "bidirectional"))
      (node (ref "J4") (pin "P$3") (pinfunction "PIN3_P$3") (pintype "bidirectional"))
      (node (ref "J5") (pin "P$13") (pinfunction "PIN13_P$13") (pintype "bidirectional"))
      (node (ref "J5") (pin "P$4") (pinfunction "PIN4_P$4") (pintype "bidirectional"))
      (node (ref "R3") (pin "P$2") (pinfunction "P$2_P$2") (pintype "passive"))
      (node (ref "R6") (pin "P$1") (pinfunction "P$1_P$1") (pintype "passive"))
      (node (ref "SW1") (pin "P$1") (pinfunction "P$1_P$1") (pintype "bidirectional"))
      (node (ref "SW1") (pin "P$2") (pinfunction "P$2_P$2") (pintype "bidirectional"))
      (node (ref "SW2") (pin "P$1") (pinfunction "P$1_P$1") (pintype "bidirectional"))
      (node (ref "SW2") (pin "P$2") (pinfunction "P$2_P$2") (pintype "bidirectional"))
      (node (ref "U1") (pin "1") (pinfunction "ADJUST/GROUND_1") (pintype "bidirectional"))
      (node (ref "U2") (pin "2") (pinfunction "GND_2") (pintype "passive"))
      (node (ref "U3") (pin "2") (pinfunction "GND_2") (pintype "passive"))
      (node (ref "U4") (pin "2") (pinfunction "VSS_2") (pintype "power_in"))
      (node (ref "U5") (pin "21") (pinfunction "AON_PSD_LFCLKSEL_21") (pintype "bidirectional"))
      (node (ref "U5") (pin "49") (pinfunction "GND_49") (pintype "bidirectional"))
      (node (ref "U6") (pin "4") (pinfunction "GND_4") (pintype "bidirectional"))
      (node (ref "U7") (pin "15") (pinfunction "VREFL_15") (pintype "bidirectional"))
      (node (ref "U7") (pin "16") (pinfunction "VSSA_16") (pintype "bidirectional"))
      (node (ref "U7") (pin "31") (pinfunction "GND_31") (pintype "bidirectional"))
      (node (ref "U7") (pin "4") (pinfunction "GND_4") (pintype "bidirectional"))
      (node (ref "U7") (pin "47") (pinfunction "GND_47") (pintype "bidirectional"))
      (node (ref "U8") (pin "1") (pinfunction "GND_1") (pintype "power_in"))
      (node (ref "X1") (pin "2") (pinfunction "2_2") (pintype "passive"))
      (node (ref "Y1") (pin "2") (pinfunction "2_2") (pintype "passive"))
      (node (ref "Y1") (pin "4") (pinfunction "4_4") (pintype "passive"))
      (node (ref "Y2") (pin "2") (pinfunction "GND_2") (pintype "passive"))
    )
    (net (code "16") (name "IO11") (class "Default")
      (node (ref "J4") (pin "P$10") (pinfunction "PIN10_P$10") (pintype "bidirectional"))
      (node (ref "U5") (pin "35") (pinfunction "IO11_35") (pintype "bidirectional"))
    )
    (net (code "17") (name "IO19") (class "Default")
      (node (ref "J5") (pin "P$7") (pinfunction "PIN7_P$7") (pintype "bidirectional"))
      (node (ref "U5") (pin "41") (pinfunction "IO19_41") (pintype "bidirectional"))
    )
    (net (code "18") (name "IO20") (class "Default")
      (node (ref "J5") (pin "P$8") (pinfunction "PIN8_P$8") (pintype "bidirectional"))
      (node (ref "U5") (pin "42") (pinfunction "IO20_42") (pintype "bidirectional"))
    )
    (net (code "19") (name "IO21") (class "Default")
      (node (ref "J5") (pin "P$9") (pinfunction "PIN9_P$9") (pintype "bidirectional"))
      (node (ref "U5") (pin "43") (pinfunction "IO21_43") (pintype "bidirectional"))
    )
    (net (code "20") (name "IO22") (class "Default")
      (node (ref "J5") (pin "P$10") (pinfunction "PIN10_P$10") (pintype "bidirectional"))
      (node (ref "U5") (pin "44") (pinfunction "IO22_44") (pintype "bidirectional"))
    )
    (net (code "21") (name "JTAG_TCK") (class "Default")
      (node (ref "J1-NEST-OWL1") (pin "15") (pinfunction "15_15") (pintype "passive"))
      (node (ref "U5") (pin "13") (pinfunction "JTAG_TCK_13") (pintype "bidirectional"))
    )
    (net (code "22") (name "JTAG_TCK_NEST") (class "Default")
      (node (ref "J1-NEST-OWL1") (pin "16") (pinfunction "16_16") (pintype "passive"))
      (node (ref "R14") (pin "P$2") (pinfunction "P$2_P$2") (pintype "passive"))
    )
    (net (code "23") (name "JTAG_TDI") (class "Default")
      (node (ref "J1-NEST-OWL1") (pin "19") (pinfunction "19_19") (pintype "passive"))
      (node (ref "U5") (pin "16") (pinfunction "JTAG_TDI_16") (pintype "bidirectional"))
    )
    (net (code "24") (name "JTAG_TDI_NEST") (class "Default")
      (node (ref "J1-NEST-OWL1") (pin "20") (pinfunction "20_20") (pintype "passive"))
      (node (ref "R13") (pin "P$2") (pinfunction "P$2_P$2") (pintype "passive"))
    )
    (net (code "25") (name "JTAG_TDO") (class "Default")
      (node (ref "J1-NEST-OWL1") (pin "17") (pinfunction "17_17") (pintype "passive"))
      (node (ref "U5") (pin "14") (pinfunction "JTAG_TDO_14") (pintype "bidirectional"))
    )
    (net (code "26") (name "JTAG_TDO_NEST") (class "Default")
      (node (ref "J1-NEST-OWL1") (pin "18") (pinfunction "18_18") (pintype "passive"))
      (node (ref "U7") (pin "2") (pinfunction "PTE1/LLWU_P0_2") (pintype "bidirectional"))
    )
    (net (code "27") (name "JTAG_TMS") (class "Default")
      (node (ref "J1-NEST-OWL1") (pin "13") (pinfunction "13_13") (pintype "passive"))
      (node (ref "U5") (pin "15") (pinfunction "JTAG_TMS_15") (pintype "bidirectional"))
    )
    (net (code "28") (name "JTAG_TMS_NEST") (class "Default")
      (node (ref "J1-NEST-OWL1") (pin "14") (pinfunction "14_14") (pintype "passive"))
      (node (ref "R15") (pin "P$1") (pinfunction "P$1_P$1") (pintype "passive"))
    )
    (net (code "29") (name "MISO") (class "Default")
      (node (ref "J4") (pin "P$6") (pinfunction "PIN6_P$6") (pintype "bidirectional"))
      (node (ref "U5") (pin "29") (pinfunction "IO4_29") (pintype "bidirectional"))
    )
    (net (code "30") (name "MOSI") (class "Default")
      (node (ref "J4") (pin "P$5") (pinfunction "PIN5_P$5") (pintype "bidirectional"))
      (node (ref "U5") (pin "28") (pinfunction "IO3_28") (pintype "bidirectional"))
    )
    (net (code "31") (name "Net-(D2-PadCATHODE)") (class "Default")
      (node (ref "D2") (pin "CATHODE") (pinfunction "CATHODE_CATHODE") (pintype "power_in"))
      (node (ref "R3") (pin "P$1") (pinfunction "P$1_P$1") (pintype "passive"))
    )
    (net (code "32") (name "Net-(D3-PadANODE)") (class "Default")
      (node (ref "D3") (pin "ANODE") (pinfunction "ANODE_ANODE") (pintype "power_in"))
      (node (ref "R4") (pin "P$2") (pinfunction "P$2_P$2") (pintype "passive"))
    )
    (net (code "33") (name "Net-(D4-PadANODE)") (class "Default")
      (node (ref "D4") (pin "ANODE") (pinfunction "ANODE_ANODE") (pintype "power_in"))
      (node (ref "R5") (pin "P$2") (pinfunction "P$2_P$2") (pintype "passive"))
    )
    (net (code "34") (name "Net-(D5-PadCATHODE)") (class "Default")
      (node (ref "D5") (pin "CATHODE") (pinfunction "CATHODE_CATHODE") (pintype "power_in"))
      (node (ref "R7") (pin "P$2") (pinfunction "P$2_P$2") (pintype "passive"))
    )
    (net (code "35") (name "Net-(U2-EN)") (class "Default")
      (node (ref "R1") (pin "P$2") (pinfunction "P$2_P$2") (pintype "passive"))
      (node (ref "U2") (pin "3") (pinfunction "EN_3") (pintype "passive"))
    )
    (net (code "36") (name "Net-(U3-EN)") (class "Default")
      (node (ref "C8") (pin "P$1") (pinfunction "P$1_P$1") (pintype "passive"))
      (node (ref "R2") (pin "P$1") (pinfunction "P$1_P$1") (pintype "passive"))
      (node (ref "U3") (pin "3") (pinfunction "EN_3") (pintype "passive"))
    )
    (net (code "37") (name "Net-(U4-PROG)") (class "Default")
      (node (ref "R6") (pin "P$2") (pinfunction "P$2_P$2") (pintype "passive"))
      (node (ref "U4") (pin "5") (pinfunction "PROG_5") (pintype "input"))
    )
    (net (code "38") (name "Net-(U4-STAT)") (class "Default")
      (node (ref "R7") (pin "P$1") (pinfunction "P$1_P$1") (pintype "passive"))
      (node (ref "U4") (pin "1") (pinfunction "STAT_1") (pintype "output"))
    )
    (net (code "39") (name "Net-(U5-PLL_AVSS)") (class "Default")
      (node (ref "C16") (pin "P$2") (pinfunction "P$2_P$2") (pintype "passive"))
      (node (ref "C17") (pin "P$2") (pinfunction "P$2_P$2") (pintype "passive"))
      (node (ref "U5") (pin "8") (pinfunction "PLL_AVSS_8") (pintype "bidirectional"))
    )
    (net (code "40") (name "Net-(U7-PTD2{slash}LLWU_P13)") (class "Default")
      (node (ref "R13") (pin "P$1") (pinfunction "P$1_P$1") (pintype "passive"))
      (node (ref "U7") (pin "59") (pinfunction "PTD2/LLWU_P13_59") (pintype "bidirectional"))
    )
    (net (code "41") (name "Net-(U7-PTD5)") (class "Default")
      (node (ref "R14") (pin "P$1") (pinfunction "P$1_P$1") (pintype "passive"))
      (node (ref "U7") (pin "62") (pinfunction "PTD5_62") (pintype "bidirectional"))
    )
    (net (code "42") (name "Net-(U7-PTD6{slash}LLWU_P15)") (class "Default")
      (node (ref "R15") (pin "P$2") (pinfunction "P$2_P$2") (pintype "passive"))
      (node (ref "U7") (pin "63") (pinfunction "PTD6/LLWU_P15_63") (pintype "bidirectional"))
    )
    (net (code "43") (name "PLL_AVDD") (class "Default")
      (node (ref "C16") (pin "P$1") (pinfunction "P$1_P$1") (pintype "passive"))
      (node (ref "C17") (pin "P$1") (pinfunction "P$1_P$1") (pintype "passive"))
      (node (ref "R8") (pin "P$2") (pinfunction "P$2_P$2") (pintype "passive"))
      (node (ref "U5") (pin "7") (pinfunction "PLL_AVDD_7") (pintype "bidirectional"))
    )
    (net (code "44") (name "PWM0_0") (class "Default")
      (node (ref "J5") (pin "P$5") (pinfunction "PIN5_P$5") (pintype "bidirectional"))
      (node (ref "U5") (pin "25") (pinfunction "IO0_25") (pintype "bidirectional"))
    )
    (net (code "45") (name "PWM0_1") (class "Default")
      (node (ref "J5") (pin "P$6") (pinfunction "PIN6_P$6") (pintype "bidirectional"))
      (node (ref "U5") (pin "26") (pinfunction "IO1_26") (pintype "bidirectional"))
    )
    (net (code "46") (name "QSPI_CS") (class "Default")
      (node (ref "R10") (pin "P$2") (pinfunction "P$2_P$2") (pintype "passive"))
      (node (ref "U5") (pin "5") (pinfunction "QSPI_CS_5") (pintype "bidirectional"))
      (node (ref "U6") (pin "1") (pinfunction "CE#_1") (pintype "bidirectional"))
    )
    (net (code "47") (name "QSPI_DQ0") (class "Default")
      (node (ref "U5") (pin "4") (pinfunction "QSPI_DQ_0_4") (pintype "bidirectional"))
      (node (ref "U6") (pin "5") (pinfunction "MOSI/IO0_5") (pintype "bidirectional"))
    )
    (net (code "48") (name "QSPI_DQ1") (class "Default")
      (node (ref "U5") (pin "3") (pinfunction "QSPI_DQ_1_3") (pintype "bidirectional"))
      (node (ref "U6") (pin "2") (pinfunction "MISO/IO1_2") (pintype "bidirectional"))
    )
    (net (code "49") (name "QSPI_DQ2") (class "Default")
      (node (ref "U5") (pin "2") (pinfunction "QSPI_DQ_2_2") (pintype "bidirectional"))
      (node (ref "U6") (pin "3") (pinfunction "WP#/IO2_3") (pintype "bidirectional"))
    )
    (net (code "50") (name "QSPI_DQ3") (class "Default")
      (node (ref "R9") (pin "P$2") (pinfunction "P$2_P$2") (pintype "passive"))
      (node (ref "U5") (pin "1") (pinfunction "QSPI_DQ_3_1") (pintype "bidirectional"))
      (node (ref "U6") (pin "7") (pinfunction "HOLD#/IO3_7") (pintype "bidirectional"))
    )
    (net (code "51") (name "QSPI_SCK") (class "Default")
      (node (ref "U5") (pin "48") (pinfunction "QSPI_SCK_48") (pintype "bidirectional"))
      (node (ref "U6") (pin "6") (pinfunction "SCK_6") (pintype "bidirectional"))
    )
    (net (code "52") (name "RESET") (class "Default")
      (node (ref "C20") (pin "P$1") (pinfunction "P$1_P$1") (pintype "passive"))
      (node (ref "D8") (pin "2") (pinfunction "C_2") (pintype "passive"))
      (node (ref "D9") (pin "A") (pinfunction "ANODE_A") (pintype "bidirectional"))
      (node (ref "J1-NEST-OWL1") (pin "21") (pinfunction "21_21") (pintype "passive"))
      (node (ref "J5") (pin "P$1") (pinfunction "PIN1_P$1") (pintype "bidirectional"))
      (node (ref "R12") (pin "P$2") (pinfunction "P$2_P$2") (pintype "passive"))
      (node (ref "SW2") (pin "P$3") (pinfunction "P$3_P$3") (pintype "bidirectional"))
      (node (ref "SW2") (pin "P$4") (pinfunction "P$4_P$4") (pintype "bidirectional"))
      (node (ref "U5") (pin "24") (pinfunction "AON_ERST_N_24") (pintype "bidirectional"))
    )
    (net (code "53") (name "RESET_NEST") (class "Default")
      (node (ref "J1-NEST-OWL1") (pin "22") (pinfunction "22_22") (pintype "passive"))
      (node (ref "U7") (pin "64") (pinfunction "PTD7_64") (pintype "bidirectional"))
    )
    (net (code "54") (name "RXI") (class "Default")
      (node (ref "J5") (pin "P$12") (pinfunction "PIN12_P$12") (pintype "bidirectional"))
      (node (ref "U5") (pin "45") (pinfunction "IO23_45") (pintype "bidirectional"))
    )
    (net (code "55") (name "SCK") (class "Default")
      (node (ref "J4") (pin "P$7") (pinfunction "PIN7_P$7") (pintype "bidirectional"))
      (node (ref "U5") (pin "31") (pinfunction "IO5_31") (pintype "bidirectional"))
    )
    (net (code "56") (name "SCL") (class "Default")
      (node (ref "J4") (pin "P$12") (pinfunction "PIN12_P$12") (pintype "bidirectional"))
      (node (ref "U5") (pin "37") (pinfunction "IO13_37") (pintype "bidirectional"))
    )
    (net (code "57") (name "SDA") (class "Default")
      (node (ref "J4") (pin "P$11") (pinfunction "PIN11_P$11") (pintype "bidirectional"))
      (node (ref "U5") (pin "36") (pinfunction "IO12_36") (pintype "bidirectional"))
    )
    (net (code "58") (name "TXO") (class "Default")
      (node (ref "J5") (pin "P$11") (pinfunction "PIN11_P$11") (pintype "bidirectional"))
      (node (ref "U5") (pin "40") (pinfunction "IO18_40") (pintype "bidirectional"))
    )
    (net (code "59") (name "UART_RX") (class "Default")
      (node (ref "J1-NEST-OWL1") (pin "11") (pinfunction "11_11") (pintype "passive"))
      (node (ref "U5") (pin "38") (pinfunction "IO16_38") (pintype "bidirectional"))
    )
    (net (code "60") (name "UART_RX_NEST") (class "Default")
      (node (ref "J1-NEST-OWL1") (pin "10") (pinfunction "10_10") (pintype "passive"))
      (node (ref "U7") (pin "39") (pinfunction "PTB16_39") (pintype "bidirectional"))
    )
    (net (code "61") (name "UART_TX") (class "Default")
      (node (ref "J1-NEST-OWL1") (pin "9") (pinfunction "9_9") (pintype "passive"))
      (node (ref "U5") (pin "39") (pinfunction "IO17_39") (pintype "bidirectional"))
    )
    (net (code "62") (name "UART_TX_NEST") (class "Default")
      (node (ref "J1-NEST-OWL1") (pin "12") (pinfunction "12_12") (pintype "passive"))
      (node (ref "U7") (pin "40") (pinfunction "PTB17_40") (pintype "bidirectional"))
    )
    (net (code "63") (name "USB_N") (class "Default")
      (node (ref "J2-USB") (pin "2") (pinfunction "D-_2") (pintype "bidirectional"))
      (node (ref "U7") (pin "6") (pinfunction "D-_6") (pintype "bidirectional"))
    )
    (net (code "64") (name "USB_P") (class "Default")
      (node (ref "J2-USB") (pin "3") (pinfunction "D+_3") (pintype "bidirectional"))
      (node (ref "U7") (pin "5") (pinfunction "D+_5") (pintype "bidirectional"))
    )
    (net (code "65") (name "VDD_CORE_EN") (class "Default")
      (node (ref "J1-NEST-OWL1") (pin "23") (pinfunction "23_23") (pintype "passive"))
      (node (ref "J5") (pin "P$3") (pinfunction "PIN3_P$3") (pintype "bidirectional"))
      (node (ref "U5") (pin "22") (pinfunction "AON_PMU_OUT_0_22") (pintype "bidirectional"))
    )
    (net (code "66") (name "V_BATT") (class "Default")
      (node (ref "C9") (pin "P$1") (pinfunction "P$1_P$1") (pintype "passive"))
      (node (ref "D6") (pin "A") (pinfunction "A_A") (pintype "passive"))
      (node (ref "U4") (pin "3") (pinfunction "VBAT_3") (pintype "power_in"))
      (node (ref "X1") (pin "1") (pinfunction "1_1") (pintype "passive"))
    )
    (net (code "67") (name "V_USB") (class "Default")
      (node (ref "C2") (pin "P$1") (pinfunction "P$1_P$1") (pintype "passive"))
      (node (ref "C3") (pin "P$1") (pinfunction "P$1_P$1") (pintype "passive"))
      (node (ref "D1") (pin "1") (pinfunction "CATHODE_1") (pintype "bidirectional"))
      (node (ref "D5") (pin "ANODE") (pinfunction "ANODE_ANODE") (pintype "power_in"))
      (node (ref "D6") (pin "C") (pinfunction "C_C") (pintype "passive"))
      (node (ref "J2-USB") (pin "1") (pinfunction "5V_1") (pintype "power_in"))
      (node (ref "U1") (pin "3") (pinfunction "INPUT_3") (pintype "input"))
      (node (ref "U4") (pin "4") (pinfunction "VDD_4") (pintype "power_in"))
    )
    (net (code "68") (name "WAKE") (class "Default")
      (node (ref "D7") (pin "2") (pinfunction "C_2") (pintype "passive"))
      (node (ref "J5") (pin "P$2") (pinfunction "PIN2_P$2") (pintype "bidirectional"))
      (node (ref "R11") (pin "P$2") (pinfunction "P$2_P$2") (pintype "passive"))
      (node (ref "SW1") (pin "P$3") (pinfunction "P$3_P$3") (pintype "bidirectional"))
      (node (ref "SW1") (pin "P$4") (pinfunction "P$4_P$4") (pintype "bidirectional"))
      (node (ref "U5") (pin "18") (pinfunction "AON_DWAKEUP_N_18") (pintype "bidirectional"))
    )
    (net (code "69") (name "unconnected-(J2-USB-ID-Pad4)") (class "Default")
      (node (ref "J2-USB") (pin "4") (pinfunction "ID_4") (pintype "bidirectional"))
    )
    (net (code "70") (name "unconnected-(U2-NC-Pad4)") (class "Default")
      (node (ref "U2") (pin "4") (pinfunction "NC_4") (pintype "passive"))
    )
    (net (code "71") (name "unconnected-(U3-NC-Pad4)") (class "Default")
      (node (ref "U3") (pin "4") (pinfunction "NC_4") (pintype "passive"))
    )
    (net (code "72") (name "unconnected-(U5-AON_PMU_OUT_1-Pad17)") (class "Default")
      (node (ref "U5") (pin "17") (pinfunction "AON_PMU_OUT_1_17") (pintype "bidirectional"))
    )
    (net (code "73") (name "unconnected-(U7-ADC0_DM0{slash}ADC1_DM3-Pad10)") (class "Default")
      (node (ref "U7") (pin "10") (pinfunction "ADC0_DM0/ADC1_DM3_10") (pintype "bidirectional"))
    )
    (net (code "74") (name "unconnected-(U7-ADC0_DP0{slash}ADC1_DP3-Pad9)") (class "Default")
      (node (ref "U7") (pin "9") (pinfunction "ADC0_DP0/ADC1_DP3_9") (pintype "bidirectional"))
    )
    (net (code "75") (name "unconnected-(U7-ADC1_DM0{slash}ADC0_DM3-Pad12)") (class "Default")
      (node (ref "U7") (pin "12") (pinfunction "ADC1_DM0/ADC0_DM3_12") (pintype "bidirectional"))
    )
    (net (code "76") (name "unconnected-(U7-ADC1_DP0{slash}ADC0_DP3-Pad11)") (class "Default")
      (node (ref "U7") (pin "11") (pinfunction "ADC1_DP0/ADC0_DP3_11") (pintype "bidirectional"))
    )
    (net (code "77") (name "unconnected-(U7-DAC0_OUT-Pad18)") (class "Default")
      (node (ref "U7") (pin "18") (pinfunction "DAC0_OUT_18") (pintype "bidirectional"))
    )
    (net (code "78") (name "unconnected-(U7-EXTAL32-Pad20)") (class "Default")
      (node (ref "U7") (pin "20") (pinfunction "EXTAL32_20") (pintype "bidirectional"))
    )
    (net (code "79") (name "unconnected-(U7-NC8-Pad8)") (class "Default")
      (node (ref "U7") (pin "8") (pinfunction "NC8_8") (pintype "bidirectional"))
    )
    (net (code "80") (name "unconnected-(U7-PTA1-Pad23)") (class "Default")
      (node (ref "U7") (pin "23") (pinfunction "PTA1_23") (pintype "bidirectional"))
    )
    (net (code "81") (name "unconnected-(U7-PTA5-Pad27)") (class "Default")
      (node (ref "U7") (pin "27") (pinfunction "PTA5_27") (pintype "bidirectional"))
    )
    (net (code "82") (name "unconnected-(U7-PTA12-Pad28)") (class "Default")
      (node (ref "U7") (pin "28") (pinfunction "PTA12_28") (pintype "bidirectional"))
    )
    (net (code "83") (name "unconnected-(U7-PTA13{slash}LLWU_P4-Pad29)") (class "Default")
      (node (ref "U7") (pin "29") (pinfunction "PTA13/LLWU_P4_29") (pintype "bidirectional"))
    )
    (net (code "84") (name "unconnected-(U7-PTA18-Pad32)") (class "Default")
      (node (ref "U7") (pin "32") (pinfunction "PTA18_32") (pintype "bidirectional"))
    )
    (net (code "85") (name "unconnected-(U7-PTA19-Pad33)") (class "Default")
      (node (ref "U7") (pin "33") (pinfunction "PTA19_33") (pintype "bidirectional"))
    )
    (net (code "86") (name "unconnected-(U7-PTB0{slash}LLWU_P5-Pad35)") (class "Default")
      (node (ref "U7") (pin "35") (pinfunction "PTB0/LLWU_P5_35") (pintype "bidirectional"))
    )
    (net (code "87") (name "unconnected-(U7-PTB1-Pad36)") (class "Default")
      (node (ref "U7") (pin "36") (pinfunction "PTB1_36") (pintype "bidirectional"))
    )
    (net (code "88") (name "unconnected-(U7-PTB2-Pad37)") (class "Default")
      (node (ref "U7") (pin "37") (pinfunction "PTB2_37") (pintype "bidirectional"))
    )
    (net (code "89") (name "unconnected-(U7-PTB3-Pad38)") (class "Default")
      (node (ref "U7") (pin "38") (pinfunction "PTB3_38") (pintype "bidirectional"))
    )
    (net (code "90") (name "unconnected-(U7-PTB18-Pad41)") (class "Default")
      (node (ref "U7") (pin "41") (pinfunction "PTB18_41") (pintype "bidirectional"))
    )
    (net (code "91") (name "unconnected-(U7-PTB19-Pad42)") (class "Default")
      (node (ref "U7") (pin "42") (pinfunction "PTB19_42") (pintype "bidirectional"))
    )
    (net (code "92") (name "unconnected-(U7-PTC0-Pad43)") (class "Default")
      (node (ref "U7") (pin "43") (pinfunction "PTC0_43") (pintype "bidirectional"))
    )
    (net (code "93") (name "unconnected-(U7-PTC1{slash}LLWU_P6-Pad44)") (class "Default")
      (node (ref "U7") (pin "44") (pinfunction "PTC1/LLWU_P6_44") (pintype "bidirectional"))
    )
    (net (code "94") (name "unconnected-(U7-PTC2-Pad45)") (class "Default")
      (node (ref "U7") (pin "45") (pinfunction "PTC2_45") (pintype "bidirectional"))
    )
    (net (code "95") (name "unconnected-(U7-PTC3{slash}LLWU_P7-Pad46)") (class "Default")
      (node (ref "U7") (pin "46") (pinfunction "PTC3/LLWU_P7_46") (pintype "bidirectional"))
    )
    (net (code "96") (name "unconnected-(U7-PTC4{slash}LLWU_P8-Pad49)") (class "Default")
      (node (ref "U7") (pin "49") (pinfunction "PTC4/LLWU_P8_49") (pintype "bidirectional"))
    )
    (net (code "97") (name "unconnected-(U7-PTC5{slash}LLWU_P9-Pad50)") (class "Default")
      (node (ref "U7") (pin "50") (pinfunction "PTC5/LLWU_P9_50") (pintype "bidirectional"))
    )
    (net (code "98") (name "unconnected-(U7-PTC6{slash}LLWU_P10-Pad51)") (class "Default")
      (node (ref "U7") (pin "51") (pinfunction "PTC6/LLWU_P10_51") (pintype "bidirectional"))
    )
    (net (code "99") (name "unconnected-(U7-PTC7-Pad52)") (class "Default")
      (node (ref "U7") (pin "52") (pinfunction "PTC7_52") (pintype "bidirectional"))
    )
    (net (code "100") (name "unconnected-(U7-PTC8-Pad53)") (class "Default")
      (node (ref "U7") (pin "53") (pinfunction "PTC8_53") (pintype "bidirectional"))
    )
    (net (code "101") (name "unconnected-(U7-PTC9-Pad54)") (class "Default")
      (node (ref "U7") (pin "54") (pinfunction "PTC9_54") (pintype "bidirectional"))
    )
    (net (code "102") (name "unconnected-(U7-PTC10-Pad55)") (class "Default")
      (node (ref "U7") (pin "55") (pinfunction "PTC10_55") (pintype "bidirectional"))
    )
    (net (code "103") (name "unconnected-(U7-PTC11{slash}LLWU_P11-Pad56)") (class "Default")
      (node (ref "U7") (pin "56") (pinfunction "PTC11/LLWU_P11_56") (pintype "bidirectional"))
    )
    (net (code "104") (name "unconnected-(U7-PTD0{slash}LLWU_P12-Pad57)") (class "Default")
      (node (ref "U7") (pin "57") (pinfunction "PTD0/LLWU_P12_57") (pintype "bidirectional"))
    )
    (net (code "105") (name "unconnected-(U7-PTD1-Pad58)") (class "Default")
      (node (ref "U7") (pin "58") (pinfunction "PTD1_58") (pintype "bidirectional"))
    )
    (net (code "106") (name "unconnected-(U7-PTD3-Pad60)") (class "Default")
      (node (ref "U7") (pin "60") (pinfunction "PTD3_60") (pintype "bidirectional"))
    )
    (net (code "107") (name "unconnected-(U7-PTD4{slash}LLWU_P14-Pad61)") (class "Default")
      (node (ref "U7") (pin "61") (pinfunction "PTD4/LLWU_P14_61") (pintype "bidirectional"))
    )
    (net (code "108") (name "unconnected-(U7-PTE0{slash}VLKOUT32K-Pad1)") (class "Default")
      (node (ref "U7") (pin "1") (pinfunction "PTE0/VLKOUT32K_1") (pintype "bidirectional"))
    )
    (net (code "109") (name "unconnected-(U7-VREF_OUT-Pad17)") (class "Default")
      (node (ref "U7") (pin "17") (pinfunction "VREF_OUT_17") (pintype "bidirectional"))
    )
    (net (code "110") (name "unconnected-(U7-XTAL32-Pad19)") (class "Default")
      (node (ref "U7") (pin "19") (pinfunction "XTAL32_19") (pintype "bidirectional"))
    )
    (net (code "111") (name "unconnected-(Y2-NC-Pad1)") (class "Default")
      (node (ref "Y2") (pin "1") (pinfunction "NC_1") (pintype "no_connect"))
    )
  )
)
